# E17-06-PDU_E17-PDU-POWER.net
KiCad netlist of a schematic drawn in Altium Designer
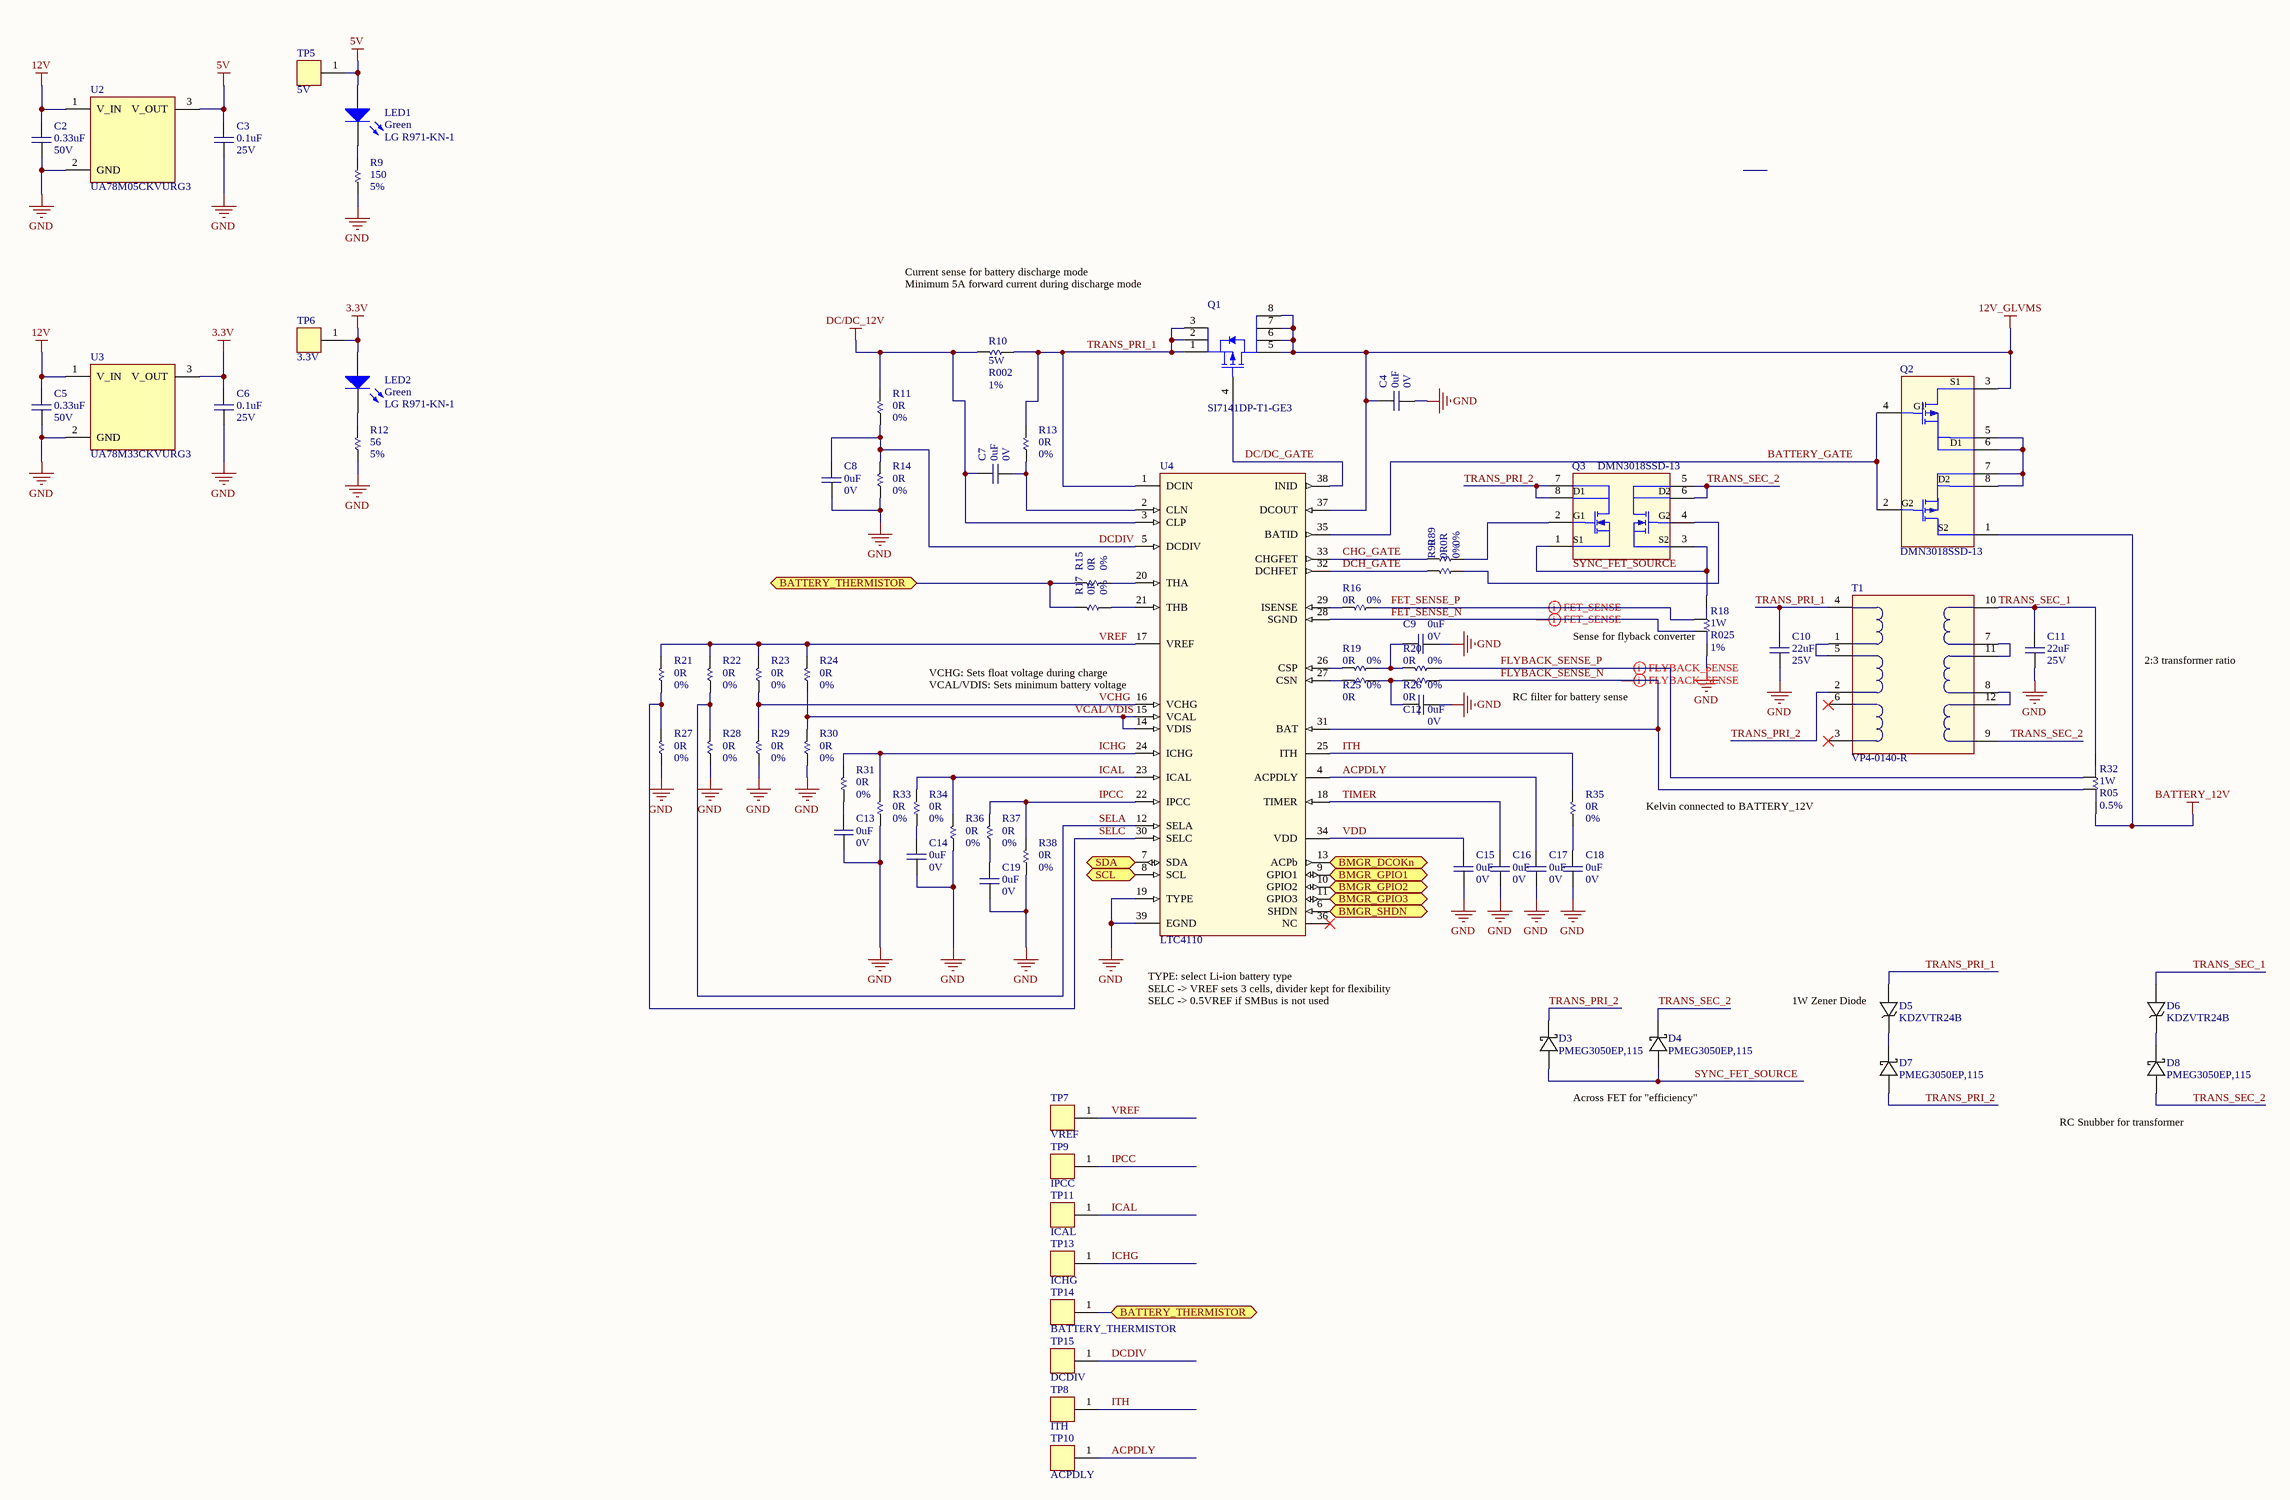
[diagram p0: E17-06-PDU_E17-PDU-POWER.SchDoc]

(export (version "E")
  (design (tool "Eeschema 10.0.6"))
  (components
    (comp (ref "C2")
      (value "0.33uF")
      (footprint "C0805")
      (description "Generic 0805 Capacitor")
      (fields
        (field (name "TOLERANCE") "10%")
        (field (name "VOLTAGE") "50V")
        (field (name "Comment") "C_0805_Generic")
      )
      (libsource (lib "Compiled_PDU") (part "C_0805_Generic"))
    )
    (comp (ref "C3")
      (value "0.1uF")
      (footprint "C0805")
      (description "Generic 0805 Capacitor")
      (fields
        (field (name "TOLERANCE") "10%")
        (field (name "VOLTAGE") "25V")
        (field (name "Comment") "C_0805_Generic")
      )
      (libsource (lib "Compiled_PDU") (part "C_0805_Generic"))
    )
    (comp (ref "C4")
      (value "0uF")
      (footprint "C0603")
      (description "Generic 0603 Capacitor")
      (fields
        (field (name "TOLERANCE") "0%")
        (field (name "VOLTAGE") "0V")
        (field (name "Comment") "C_0603_Generic_1")
      )
      (libsource (lib "Compiled_PDU") (part "C_0603_Generic_1"))
    )
    (comp (ref "C5")
      (value "0.33uF")
      (footprint "C0805")
      (description "Generic 0805 Capacitor")
      (fields
        (field (name "TOLERANCE") "10%")
        (field (name "VOLTAGE") "50V")
        (field (name "Comment") "C_0805_Generic")
      )
      (libsource (lib "Compiled_PDU") (part "C_0805_Generic"))
    )
    (comp (ref "C6")
      (value "0.1uF")
      (footprint "C0805")
      (description "Generic 0805 Capacitor")
      (fields
        (field (name "TOLERANCE") "10%")
        (field (name "VOLTAGE") "25V")
        (field (name "Comment") "C_0805_Generic")
      )
      (libsource (lib "Compiled_PDU") (part "C_0805_Generic"))
    )
    (comp (ref "C7")
      (value "0uF")
      (footprint "C0603")
      (description "Generic 0603 Capacitor")
      (fields
        (field (name "TOLERANCE") "0%")
        (field (name "VOLTAGE") "0V")
        (field (name "Comment") "C_0603_Generic_1")
      )
      (libsource (lib "Compiled_PDU") (part "C_0603_Generic_1"))
    )
    (comp (ref "C8")
      (value "0uF")
      (footprint "C0603")
      (description "Generic 0603 Capacitor")
      (fields
        (field (name "TOLERANCE") "0%")
        (field (name "VOLTAGE") "0V")
        (field (name "Comment") "C_0603_Generic_1")
      )
      (libsource (lib "Compiled_PDU") (part "C_0603_Generic_1"))
    )
    (comp (ref "C9")
      (value "0uF")
      (footprint "C0402")
      (description "Generic 0402 Capacitor")
      (fields
        (field (name "TOLERANCE") "0%")
        (field (name "VOLTAGE") "0V")
        (field (name "Comment") "C_0403_Generic")
      )
      (libsource (lib "Compiled_PDU") (part "C_0403_Generic"))
    )
    (comp (ref "C10")
      (value "22uF")
      (footprint "C0805")
      (description "Generic 0805 Capacitor")
      (fields
        (field (name "TOLERANCE") "20%")
        (field (name "VOLTAGE") "25V")
        (field (name "Comment") "C_0805_Generic")
      )
      (libsource (lib "Compiled_PDU") (part "C_0805_Generic"))
    )
    (comp (ref "C11")
      (value "22uF")
      (footprint "C0805")
      (description "Generic 0805 Capacitor")
      (fields
        (field (name "TOLERANCE") "20%")
        (field (name "VOLTAGE") "25V")
        (field (name "Comment") "C_0805_Generic")
      )
      (libsource (lib "Compiled_PDU") (part "C_0805_Generic"))
    )
    (comp (ref "C12")
      (value "0uF")
      (footprint "C0402")
      (description "Generic 0402 Capacitor")
      (fields
        (field (name "TOLERANCE") "0%")
        (field (name "VOLTAGE") "0V")
        (field (name "Comment") "C_0403_Generic")
      )
      (libsource (lib "Compiled_PDU") (part "C_0403_Generic"))
    )
    (comp (ref "C13")
      (value "0uF")
      (footprint "C0402")
      (description "Generic 0402 Capacitor")
      (fields
        (field (name "TOLERANCE") "0%")
        (field (name "VOLTAGE") "0V")
        (field (name "Comment") "C_0403_Generic")
      )
      (libsource (lib "Compiled_PDU") (part "C_0403_Generic"))
    )
    (comp (ref "C14")
      (value "0uF")
      (footprint "C0402")
      (description "Generic 0402 Capacitor")
      (fields
        (field (name "TOLERANCE") "0%")
        (field (name "VOLTAGE") "0V")
        (field (name "Comment") "C_0403_Generic")
      )
      (libsource (lib "Compiled_PDU") (part "C_0403_Generic"))
    )
    (comp (ref "C15")
      (value "0uF")
      (footprint "C0603")
      (description "Generic 0603 Capacitor")
      (fields
        (field (name "TOLERANCE") "0%")
        (field (name "VOLTAGE") "0V")
        (field (name "Comment") "C_0603_Generic_1")
      )
      (libsource (lib "Compiled_PDU") (part "C_0603_Generic_1"))
    )
    (comp (ref "C16")
      (value "0uF")
      (footprint "C0402")
      (description "Generic 0402 Capacitor")
      (fields
        (field (name "TOLERANCE") "0%")
        (field (name "VOLTAGE") "0V")
        (field (name "Comment") "C_0403_Generic")
      )
      (libsource (lib "Compiled_PDU") (part "C_0403_Generic"))
    )
    (comp (ref "C17")
      (value "0uF")
      (footprint "C0402")
      (description "Generic 0402 Capacitor")
      (fields
        (field (name "TOLERANCE") "0%")
        (field (name "VOLTAGE") "0V")
        (field (name "Comment") "C_0403_Generic")
      )
      (libsource (lib "Compiled_PDU") (part "C_0403_Generic"))
    )
    (comp (ref "C18")
      (value "0uF")
      (footprint "C0402")
      (description "Generic 0402 Capacitor")
      (fields
        (field (name "TOLERANCE") "0%")
        (field (name "VOLTAGE") "0V")
        (field (name "Comment") "C_0403_Generic")
      )
      (libsource (lib "Compiled_PDU") (part "C_0403_Generic"))
    )
    (comp (ref "C19")
      (value "0uF")
      (footprint "C0402")
      (description "Generic 0402 Capacitor")
      (fields
        (field (name "TOLERANCE") "0%")
        (field (name "VOLTAGE") "0V")
        (field (name "Comment") "C_0403_Generic")
      )
      (libsource (lib "Compiled_PDU") (part "C_0403_Generic"))
    )
    (comp (ref "D3")
      (value "D_PMEG3050EP,115")
      (footprint "SOD-128")
      (description "DIODE SCHOTTKY 360mV 30V 5A")
      (fields (field (name "MFG") "Nexperia") (field (name "MFG_PN") "PMEG3050EP,115"))
      (libsource (lib "Compiled_PDU") (part "D_PMEG3050EP,115"))
    )
    (comp (ref "D4")
      (value "D_PMEG3050EP,115")
      (footprint "SOD-128")
      (description "DIODE SCHOTTKY 360mV 30V 5A")
      (fields (field (name "MFG") "Nexperia") (field (name "MFG_PN") "PMEG3050EP,115"))
      (libsource (lib "Compiled_PDU") (part "D_PMEG3050EP,115"))
    )
    (comp (ref "D5")
      (value "D_ZENER")
      (footprint "Compiled_PDU:SOD-123FL")
      (description "DIODE ZENER 24V 1W PMDU")
      (fields (field (name "MFG") "Rohm Semiconductor") (field (name "MFG_PN") "KDZVTR24B"))
      (libsource (lib "Compiled_PDU") (part "D_ZENER"))
    )
    (comp (ref "D6")
      (value "D_ZENER")
      (footprint "Compiled_PDU:SOD-123FL")
      (description "DIODE ZENER 24V 1W PMDU")
      (fields (field (name "MFG") "Rohm Semiconductor") (field (name "MFG_PN") "KDZVTR24B"))
      (libsource (lib "Compiled_PDU") (part "D_ZENER"))
    )
    (comp (ref "D7")
      (value "D_PMEG3050EP,115")
      (footprint "SOD-128")
      (description "DIODE SCHOTTKY 360mV 30V 5A")
      (fields (field (name "MFG") "Nexperia") (field (name "MFG_PN") "PMEG3050EP,115"))
      (libsource (lib "Compiled_PDU") (part "D_PMEG3050EP,115"))
    )
    (comp (ref "D8")
      (value "D_PMEG3050EP,115")
      (footprint "SOD-128")
      (description "DIODE SCHOTTKY 360mV 30V 5A")
      (fields (field (name "MFG") "Nexperia") (field (name "MFG_PN") "PMEG3050EP,115"))
      (libsource (lib "Compiled_PDU") (part "D_PMEG3050EP,115"))
    )
    (comp (ref "LED1")
      (value "Green")
      (footprint "LGR971")
      (description "Green LED")
      (fields (field (name "MFG") "OSRAM Opto Semiconductors Inc.") (field (name "MFG_PN") "LG R971-KN-1"))
      (libsource (lib "Compiled_PDU") (part "LED_LGR971"))
    )
    (comp (ref "LED2")
      (value "Green")
      (footprint "LGR971")
      (description "Green LED")
      (fields (field (name "MFG") "OSRAM Opto Semiconductors Inc.") (field (name "MFG_PN") "LG R971-KN-1"))
      (libsource (lib "Compiled_PDU") (part "LED_LGR971"))
    )
    (comp (ref "Q1")
      (value "Q_SI7141DP-T1-GE3")
      (footprint "PowerPak SO-8")
      (description "P-CH 20V 60A PowerPak SO-8")
      (fields (field (name "MFG") "Vishay") (field (name "MFG_PN") "SI7141DP-T1-GE3"))
      (libsource (lib "Compiled_PDU") (part "Q_SI7141DP-T1-GE3"))
    )
    (comp (ref "Q2")
      (value "Q_DMN3018SSD-13_1")
      (footprint "8-SOIC")
      (description "2x P-ch FET 40V 6.7A")
      (fields (field (name "MFG") "ON Semiconductor") (field (name "MFG_PN") "DMN3018SSD-13"))
      (libsource (lib "Compiled_PDU") (part "Q_DMN3018SSD-13_1"))
    )
    (comp (ref "Q3")
      (value "Q_DMN3018SSD-13")
      (footprint "8-SOIC")
      (description "2x N-ch FET 40V 6.7A")
      (fields (field (name "MFG") "ON Semiconductor") (field (name "MFG_PN") "DMN3018SSD-13"))
      (libsource (lib "Compiled_PDU") (part "Q_DMN3018SSD-13"))
    )
    (comp (ref "R9")
      (value "150")
      (footprint "R0805")
      (description "Generic 0805 Resistor")
      (fields
        (field (name "POWER") "1/8W")
        (field (name "TOLERANCE") "5%")
        (field (name "Comment") "R_0805_Generic")
      )
      (libsource (lib "Compiled_PDU") (part "R_0805_Generic"))
    )
    (comp (ref "R10")
      (value "R002")
      (footprint "R2526")
      (description "RES CURRENT SENSE R002 1% 5W")
      (fields
        (field (name "MFG") "Panasonic")
        (field (name "POWER") "5W")
        (field (name "TOLERANCE") "1%")
        (field (name "Comment") "R_ERJ-MS6SF2M0U")
      )
      (libsource (lib "Compiled_PDU") (part "R_ERJ-MS6SF2M0U"))
    )
    (comp (ref "R11")
      (value "0R")
      (footprint "R0603")
      (description "Generic 0603 Resistor")
      (fields
        (field (name "POWER") "0W")
        (field (name "TOLERANCE") "0%")
        (field (name "Comment") "R_0603_Generic")
      )
      (libsource (lib "Compiled_PDU") (part "R_0603_Generic"))
    )
    (comp (ref "R12")
      (value "56")
      (footprint "R0805")
      (description "Generic 0805 Resistor")
      (fields
        (field (name "POWER") "1/8W")
        (field (name "TOLERANCE") "5%")
        (field (name "Comment") "R_0805_Generic")
      )
      (libsource (lib "Compiled_PDU") (part "R_0805_Generic"))
    )
    (comp (ref "R13")
      (value "0R")
      (footprint "R0603")
      (description "Generic 0603 Resistor")
      (fields
        (field (name "POWER") "0W")
        (field (name "TOLERANCE") "0%")
        (field (name "Comment") "R_0603_Generic")
      )
      (libsource (lib "Compiled_PDU") (part "R_0603_Generic"))
    )
    (comp (ref "R14")
      (value "0R")
      (footprint "R0603")
      (description "Generic 0603 Resistor")
      (fields
        (field (name "POWER") "0W")
        (field (name "TOLERANCE") "0%")
        (field (name "Comment") "R_0603_Generic")
      )
      (libsource (lib "Compiled_PDU") (part "R_0603_Generic"))
    )
    (comp (ref "R15")
      (value "0R")
      (footprint "R0603")
      (description "Generic 0603 Resistor")
      (fields
        (field (name "POWER") "0W")
        (field (name "TOLERANCE") "0%")
        (field (name "Comment") "R_0603_Generic")
      )
      (libsource (lib "Compiled_PDU") (part "R_0603_Generic"))
    )
    (comp (ref "R16")
      (value "0R")
      (footprint "R0402")
      (description "Generic 0402 Resistor")
      (fields
        (field (name "POWER") "0W")
        (field (name "TOLERANCE") "0%")
        (field (name "Comment") "R_0402_Generic")
      )
      (libsource (lib "Compiled_PDU") (part "R_0402_Generic"))
    )
    (comp (ref "R17")
      (value "0R")
      (footprint "R0603")
      (description "Generic 0603 Resistor")
      (fields
        (field (name "POWER") "0W")
        (field (name "TOLERANCE") "0%")
        (field (name "Comment") "R_0603_Generic")
      )
      (libsource (lib "Compiled_PDU") (part "R_0603_Generic"))
    )
    (comp (ref "R18")
      (value "R025")
      (footprint "R2512")
      (description "RES CURRENT SENSE R025 1% 1W")
      (fields
        (field (name "MFG") "Ohmite")
        (field (name "POWER") "1W")
        (field (name "TOLERANCE") "1%")
        (field (name "Comment") "R_LVK24R025FER")
      )
      (libsource (lib "Compiled_PDU") (part "R_LVK24R025FER"))
    )
    (comp (ref "R19")
      (value "0R")
      (footprint "R0402")
      (description "Generic 0402 Resistor")
      (fields
        (field (name "POWER") "0W")
        (field (name "TOLERANCE") "0%")
        (field (name "Comment") "R_0402_Generic")
      )
      (libsource (lib "Compiled_PDU") (part "R_0402_Generic"))
    )
    (comp (ref "R20")
      (value "0R")
      (footprint "R0402")
      (description "Generic 0402 Resistor")
      (fields
        (field (name "POWER") "0W")
        (field (name "TOLERANCE") "0%")
        (field (name "Comment") "R_0402_Generic")
      )
      (libsource (lib "Compiled_PDU") (part "R_0402_Generic"))
    )
    (comp (ref "R21")
      (value "0R")
      (footprint "R0402")
      (description "Generic 0402 Resistor")
      (fields
        (field (name "POWER") "0W")
        (field (name "TOLERANCE") "0%")
        (field (name "Comment") "R_0402_Generic")
      )
      (libsource (lib "Compiled_PDU") (part "R_0402_Generic"))
    )
    (comp (ref "R22")
      (value "0R")
      (footprint "R0402")
      (description "Generic 0402 Resistor")
      (fields
        (field (name "POWER") "0W")
        (field (name "TOLERANCE") "0%")
        (field (name "Comment") "R_0402_Generic")
      )
      (libsource (lib "Compiled_PDU") (part "R_0402_Generic"))
    )
    (comp (ref "R23")
      (value "0R")
      (footprint "R0402")
      (description "Generic 0402 Resistor")
      (fields
        (field (name "POWER") "0W")
        (field (name "TOLERANCE") "0%")
        (field (name "Comment") "R_0402_Generic")
      )
      (libsource (lib "Compiled_PDU") (part "R_0402_Generic"))
    )
    (comp (ref "R24")
      (value "0R")
      (footprint "R0402")
      (description "Generic 0402 Resistor")
      (fields
        (field (name "POWER") "0W")
        (field (name "TOLERANCE") "0%")
        (field (name "Comment") "R_0402_Generic")
      )
      (libsource (lib "Compiled_PDU") (part "R_0402_Generic"))
    )
    (comp (ref "R25")
      (value "0R")
      (footprint "R0402")
      (description "Generic 0402 Resistor")
      (fields
        (field (name "POWER") "0W")
        (field (name "TOLERANCE") "0%")
        (field (name "Comment") "R_0402_Generic")
      )
      (libsource (lib "Compiled_PDU") (part "R_0402_Generic"))
    )
    (comp (ref "R26")
      (value "0R")
      (footprint "R0402")
      (description "Generic 0402 Resistor")
      (fields
        (field (name "POWER") "0W")
        (field (name "TOLERANCE") "0%")
        (field (name "Comment") "R_0402_Generic")
      )
      (libsource (lib "Compiled_PDU") (part "R_0402_Generic"))
    )
    (comp (ref "R27")
      (value "0R")
      (footprint "R0402")
      (description "Generic 0402 Resistor")
      (fields
        (field (name "POWER") "0W")
        (field (name "TOLERANCE") "0%")
        (field (name "Comment") "R_0402_Generic")
      )
      (libsource (lib "Compiled_PDU") (part "R_0402_Generic"))
    )
    (comp (ref "R28")
      (value "0R")
      (footprint "R0402")
      (description "Generic 0402 Resistor")
      (fields
        (field (name "POWER") "0W")
        (field (name "TOLERANCE") "0%")
        (field (name "Comment") "R_0402_Generic")
      )
      (libsource (lib "Compiled_PDU") (part "R_0402_Generic"))
    )
    (comp (ref "R29")
      (value "0R")
      (footprint "R0402")
      (description "Generic 0402 Resistor")
      (fields
        (field (name "POWER") "0W")
        (field (name "TOLERANCE") "0%")
        (field (name "Comment") "R_0402_Generic")
      )
      (libsource (lib "Compiled_PDU") (part "R_0402_Generic"))
    )
    (comp (ref "R30")
      (value "0R")
      (footprint "R0402")
      (description "Generic 0402 Resistor")
      (fields
        (field (name "POWER") "0W")
        (field (name "TOLERANCE") "0%")
        (field (name "Comment") "R_0402_Generic")
      )
      (libsource (lib "Compiled_PDU") (part "R_0402_Generic"))
    )
    (comp (ref "R31")
      (value "0R")
      (footprint "R0402")
      (description "Generic 0402 Resistor")
      (fields
        (field (name "POWER") "0W")
        (field (name "TOLERANCE") "0%")
        (field (name "Comment") "R_0402_Generic")
      )
      (libsource (lib "Compiled_PDU") (part "R_0402_Generic"))
    )
    (comp (ref "R32")
      (value "R05")
      (footprint "R2512")
      (description "RES CURRENT SENSE R05 0.5% 1W")
      (fields
        (field (name "MFG") "Ohmite")
        (field (name "POWER") "1W")
        (field (name "TOLERANCE") "0.5%")
        (field (name "Comment") "R_LVK24R050DER")
      )
      (libsource (lib "Compiled_PDU") (part "R_LVK24R050DER"))
    )
    (comp (ref "R33")
      (value "0R")
      (footprint "R0402")
      (description "Generic 0402 Resistor")
      (fields
        (field (name "POWER") "0W")
        (field (name "TOLERANCE") "0%")
        (field (name "Comment") "R_0402_Generic")
      )
      (libsource (lib "Compiled_PDU") (part "R_0402_Generic"))
    )
    (comp (ref "R34")
      (value "0R")
      (footprint "R0402")
      (description "Generic 0402 Resistor")
      (fields
        (field (name "POWER") "0W")
        (field (name "TOLERANCE") "0%")
        (field (name "Comment") "R_0402_Generic")
      )
      (libsource (lib "Compiled_PDU") (part "R_0402_Generic"))
    )
    (comp (ref "R35")
      (value "0R")
      (footprint "R0402")
      (description "Generic 0402 Resistor")
      (fields
        (field (name "POWER") "0W")
        (field (name "TOLERANCE") "0%")
        (field (name "Comment") "R_0402_Generic")
      )
      (libsource (lib "Compiled_PDU") (part "R_0402_Generic"))
    )
    (comp (ref "R36")
      (value "0R")
      (footprint "R0402")
      (description "Generic 0402 Resistor")
      (fields
        (field (name "POWER") "0W")
        (field (name "TOLERANCE") "0%")
        (field (name "Comment") "R_0402_Generic")
      )
      (libsource (lib "Compiled_PDU") (part "R_0402_Generic"))
    )
    (comp (ref "R37")
      (value "0R")
      (footprint "R0402")
      (description "Generic 0402 Resistor")
      (fields
        (field (name "POWER") "0W")
        (field (name "TOLERANCE") "0%")
        (field (name "Comment") "R_0402_Generic")
      )
      (libsource (lib "Compiled_PDU") (part "R_0402_Generic"))
    )
    (comp (ref "R38")
      (value "0R")
      (footprint "R0402")
      (description "Generic 0402 Resistor")
      (fields
        (field (name "POWER") "0W")
        (field (name "TOLERANCE") "0%")
        (field (name "Comment") "R_0402_Generic")
      )
      (libsource (lib "Compiled_PDU") (part "R_0402_Generic"))
    )
    (comp (ref "R89")
      (value "0R")
      (footprint "R0603")
      (description "Generic 0603 Resistor")
      (fields
        (field (name "POWER") "0W")
        (field (name "TOLERANCE") "0%")
        (field (name "Comment") "R_0603_Generic")
      )
      (libsource (lib "Compiled_PDU") (part "R_0603_Generic"))
    )
    (comp (ref "R90")
      (value "0R")
      (footprint "R0603")
      (description "Generic 0603 Resistor")
      (fields
        (field (name "POWER") "0W")
        (field (name "TOLERANCE") "0%")
        (field (name "Comment") "R_0603_Generic")
      )
      (libsource (lib "Compiled_PDU") (part "R_0603_Generic"))
    )
    (comp (ref "T1")
      (value "T_VP4-0140-R")
      (footprint "T_VP4-0140-R")
      (description "Transformer 6 coil 11.3uH")
      (fields (field (name "MFG") "Eaton") (field (name "MFG_PN") "VP4-0140-R"))
      (libsource (lib "Compiled_PDU") (part "T_VP4-0140-R"))
    )
    (comp (ref "TP5")
      (value "5V")
      (footprint "TEST POINT")
      (description "Test Point")
      (libsource (lib "Compiled_PDU") (part "Test Point"))
    )
    (comp (ref "TP6")
      (value "3.3V")
      (footprint "TEST POINT")
      (description "Test Point")
      (libsource (lib "Compiled_PDU") (part "Test Point"))
    )
    (comp (ref "TP7")
      (value "VREF")
      (footprint "TEST POINT")
      (description "Test Point")
      (libsource (lib "Compiled_PDU") (part "Test Point"))
    )
    (comp (ref "TP8")
      (value "ITH")
      (footprint "TEST POINT")
      (description "Test Point")
      (libsource (lib "Compiled_PDU") (part "Test Point"))
    )
    (comp (ref "TP9")
      (value "IPCC")
      (footprint "TEST POINT")
      (description "Test Point")
      (libsource (lib "Compiled_PDU") (part "Test Point"))
    )
    (comp (ref "TP10")
      (value "ACPDLY")
      (footprint "TEST POINT")
      (description "Test Point")
      (libsource (lib "Compiled_PDU") (part "Test Point"))
    )
    (comp (ref "TP11")
      (value "ICAL")
      (footprint "TEST POINT")
      (description "Test Point")
      (libsource (lib "Compiled_PDU") (part "Test Point"))
    )
    (comp (ref "TP13")
      (value "ICHG")
      (footprint "TEST POINT")
      (description "Test Point")
      (libsource (lib "Compiled_PDU") (part "Test Point"))
    )
    (comp (ref "TP14")
      (value "BATTERY_THERMISTOR")
      (footprint "TEST POINT")
      (description "Test Point")
      (libsource (lib "Compiled_PDU") (part "Test Point"))
    )
    (comp (ref "TP15")
      (value "DCDIV")
      (footprint "TEST POINT")
      (description "Test Point")
      (libsource (lib "Compiled_PDU") (part "Test Point"))
    )
    (comp (ref "U2")
      (value "U_UA78M05CKVURG3")
      (footprint "TO-252-3")
      (description "5V 500mA Linear Regulator")
      (fields (field (name "MFG") "TI") (field (name "MFG_PN") "UA78M05CKVURG3"))
      (libsource (lib "Compiled_PDU") (part "U_UA78M05CKVURG3"))
    )
    (comp (ref "U3")
      (value "U_UA78M33CKVURG3")
      (footprint "TO-252-3")
      (description "3.3V 500mA Linear Regulator")
      (fields (field (name "MFG") "TI") (field (name "MFG_PN") "UA78M33CKVURG3"))
      (libsource (lib "Compiled_PDU") (part "U_UA78M33CKVURG3"))
    )
    (comp (ref "U4")
      (value "U_LTC4110")
      (footprint "U_LTC4110")
      (description "IC Battery Backup Manager")
      (fields (field (name "MFG") "Linear Technology") (field (name "MFG_PN") "LTC4110"))
      (libsource (lib "Compiled_PDU") (part "U_LTC4110"))
    )
  )
  (nets
    (net (code "1") (name "/ACPDLY") (class "Default")
      (node (ref "C17") (pin "1") (pinfunction "EGND_1") (pintype "passive"))
      (node (ref "TP10") (pin "1") (pintype "passive"))
      (node (ref "U4") (pin "4") (pinfunction "ACPDLY_4") (pintype "passive"))
    )
    (net (code "2") (name "/BATTERY_GATE") (class "Default")
      (node (ref "Q2") (pin "2") (pintype "passive"))
      (node (ref "Q2") (pin "4") (pinfunction "4_4") (pintype "passive"))
      (node (ref "U4") (pin "35") (pinfunction "BATID_35") (pintype "output"))
    )
    (net (code "3") (name "/BATTERY_THERMISTOR") (class "Default")
      (node (ref "R15") (pin "1") (pinfunction "1_1") (pintype "passive"))
      (node (ref "R17") (pin "1") (pinfunction "1_1") (pintype "passive"))
      (node (ref "TP14") (pin "1") (pintype "passive"))
    )
    (net (code "4") (name "/BMGR_DCOKn") (class "Default")
      (node (ref "U4") (pin "13") (pinfunction "ACPb_13") (pintype "output"))
    )
    (net (code "5") (name "/BMGR_GPIO1") (class "Default")
      (node (ref "U4") (pin "9") (pinfunction "GPIO1_9") (pintype "bidirectional"))
    )
    (net (code "6") (name "/BMGR_GPIO2") (class "Default")
      (node (ref "U4") (pin "10") (pinfunction "GPIO2_10") (pintype "bidirectional"))
    )
    (net (code "7") (name "/BMGR_GPIO3") (class "Default")
      (node (ref "U4") (pin "11") (pinfunction "GPIO3_11") (pintype "bidirectional"))
    )
    (net (code "8") (name "/BMGR_SHDN") (class "Default")
      (node (ref "U4") (pin "6") (pinfunction "SHDN_6") (pintype "input"))
    )
    (net (code "9") (name "/CHG_GATE") (class "Default")
      (node (ref "R89") (pin "1") (pinfunction "1_1") (pintype "passive"))
      (node (ref "U4") (pin "33") (pinfunction "CHGFET_33") (pintype "output"))
    )
    (net (code "10") (name "/DCDIV") (class "Default")
      (node (ref "C8") (pin "1") (pinfunction "EGND_1") (pintype "passive"))
      (node (ref "R11") (pin "2") (pinfunction "2_2") (pintype "passive"))
      (node (ref "R14") (pin "1") (pinfunction "1_1") (pintype "passive"))
      (node (ref "TP15") (pin "1") (pintype "passive"))
      (node (ref "U4") (pin "5") (pinfunction "DCDIV_5") (pintype "input"))
    )
    (net (code "11") (name "/DCH_GATE") (class "Default")
      (node (ref "R90") (pin "1") (pinfunction "1_1") (pintype "passive"))
      (node (ref "U4") (pin "32") (pinfunction "DCHFET_32") (pintype "output"))
    )
    (net (code "12") (name "/DC{slash}DC_GATE") (class "Default")
      (node (ref "Q1") (pin "4") (pinfunction "G_4") (pintype "passive"))
      (node (ref "U4") (pin "38") (pinfunction "INID_38") (pintype "output"))
    )
    (net (code "13") (name "/FET_SENSE_N") (class "Default")
      (node (ref "R18") (pin "3") (pinfunction "3_3") (pintype "passive"))
      (node (ref "U4") (pin "28") (pinfunction "SGND_28") (pintype "input"))
    )
    (net (code "14") (name "/FET_SENSE_P") (class "Default")
      (node (ref "R16") (pin "2") (pinfunction "2_2") (pintype "passive"))
      (node (ref "R18") (pin "4") (pinfunction "4_4") (pintype "passive"))
    )
    (net (code "15") (name "/FLYBACK_SENSE_N") (class "Default")
      (node (ref "R26") (pin "2") (pinfunction "2_2") (pintype "passive"))
      (node (ref "R32") (pin "3") (pinfunction "3_3") (pintype "passive"))
      (node (ref "U4") (pin "31") (pinfunction "BAT_31") (pintype "input"))
    )
    (net (code "16") (name "/FLYBACK_SENSE_P") (class "Default")
      (node (ref "R20") (pin "2") (pinfunction "2_2") (pintype "passive"))
      (node (ref "R32") (pin "4") (pinfunction "4_4") (pintype "passive"))
    )
    (net (code "17") (name "/ICAL") (class "Default")
      (node (ref "R34") (pin "1") (pinfunction "1_1") (pintype "passive"))
      (node (ref "R36") (pin "1") (pinfunction "1_1") (pintype "passive"))
      (node (ref "TP11") (pin "1") (pintype "passive"))
      (node (ref "U4") (pin "23") (pinfunction "ICAL_23") (pintype "input"))
    )
    (net (code "18") (name "/ICHG") (class "Default")
      (node (ref "R31") (pin "1") (pinfunction "1_1") (pintype "passive"))
      (node (ref "R33") (pin "1") (pinfunction "1_1") (pintype "passive"))
      (node (ref "TP13") (pin "1") (pintype "passive"))
      (node (ref "U4") (pin "24") (pinfunction "ICHG_24") (pintype "input"))
    )
    (net (code "19") (name "/IPCC") (class "Default")
      (node (ref "R37") (pin "1") (pinfunction "1_1") (pintype "passive"))
      (node (ref "R38") (pin "1") (pinfunction "1_1") (pintype "passive"))
      (node (ref "TP9") (pin "1") (pintype "passive"))
      (node (ref "U4") (pin "22") (pinfunction "IPCC_22") (pintype "input"))
    )
    (net (code "20") (name "/ITH") (class "Default")
      (node (ref "R35") (pin "1") (pinfunction "1_1") (pintype "passive"))
      (node (ref "TP8") (pin "1") (pintype "passive"))
      (node (ref "U4") (pin "25") (pinfunction "ITH_25") (pintype "passive"))
    )
    (net (code "21") (name "/SCL") (class "Default")
      (node (ref "U4") (pin "8") (pinfunction "SCL_8") (pintype "input"))
    )
    (net (code "22") (name "/SDA") (class "Default")
      (node (ref "U4") (pin "7") (pinfunction "SDA_7") (pintype "bidirectional"))
    )
    (net (code "23") (name "/SELA") (class "Default")
      (node (ref "R22") (pin "2") (pinfunction "2_2") (pintype "passive"))
      (node (ref "R28") (pin "1") (pinfunction "1_1") (pintype "passive"))
      (node (ref "U4") (pin "12") (pinfunction "SELA_12") (pintype "input"))
    )
    (net (code "24") (name "/SELC") (class "Default")
      (node (ref "R21") (pin "2") (pinfunction "2_2") (pintype "passive"))
      (node (ref "R27") (pin "1") (pinfunction "1_1") (pintype "passive"))
      (node (ref "U4") (pin "30") (pinfunction "SELC_30") (pintype "input"))
    )
    (net (code "25") (name "/SYNC_FET_SOURCE") (class "Default")
      (node (ref "D3") (pin "1") (pintype "passive"))
      (node (ref "D4") (pin "1") (pintype "passive"))
      (node (ref "Q3") (pin "1") (pintype "passive"))
      (node (ref "Q3") (pin "3") (pinfunction "3_3") (pintype "passive"))
      (node (ref "R18") (pin "2") (pinfunction "2_2") (pintype "passive"))
    )
    (net (code "26") (name "/TIMER") (class "Default")
      (node (ref "C16") (pin "1") (pinfunction "EGND_1") (pintype "passive"))
      (node (ref "U4") (pin "18") (pinfunction "TIMER_18") (pintype "input"))
    )
    (net (code "27") (name "/TRANS_PRI_1") (class "Default")
      (node (ref "C10") (pin "1") (pinfunction "EGND_1") (pintype "passive"))
      (node (ref "D5") (pin "1") (pintype "passive"))
      (node (ref "Q1") (pin "1") (pintype "passive"))
      (node (ref "Q1") (pin "2") (pinfunction "5_2") (pintype "passive"))
      (node (ref "Q1") (pin "3") (pinfunction "6_3") (pintype "passive"))
      (node (ref "R10") (pin "2") (pinfunction "2_2") (pintype "passive"))
      (node (ref "R13") (pin "1") (pinfunction "1_1") (pintype "passive"))
      (node (ref "T1") (pin "4") (pinfunction "4_4") (pintype "passive"))
      (node (ref "U4") (pin "1") (pinfunction "DCIN_1") (pintype "power_in"))
    )
    (net (code "28") (name "/TRANS_PRI_2") (class "Default")
      (node (ref "D3") (pin "2") (pintype "passive"))
      (node (ref "D7") (pin "1") (pintype "passive"))
      (node (ref "Q3") (pin "7") (pinfunction "7_7") (pintype "passive"))
      (node (ref "Q3") (pin "8") (pinfunction "8_8") (pintype "passive"))
      (node (ref "T1") (pin "2") (pinfunction "2_2") (pintype "passive"))
    )
    (net (code "29") (name "/TRANS_SEC_1") (class "Default")
      (node (ref "C11") (pin "1") (pinfunction "EGND_1") (pintype "passive"))
      (node (ref "D6") (pin "1") (pintype "passive"))
      (node (ref "R32") (pin "2") (pinfunction "2_2") (pintype "passive"))
      (node (ref "T1") (pin "10") (pinfunction "10_10") (pintype "passive"))
    )
    (net (code "30") (name "/TRANS_SEC_2") (class "Default")
      (node (ref "D4") (pin "2") (pintype "passive"))
      (node (ref "D8") (pin "1") (pintype "passive"))
      (node (ref "Q3") (pin "5") (pinfunction "5_5") (pintype "passive"))
      (node (ref "Q3") (pin "6") (pinfunction "6_6") (pintype "passive"))
      (node (ref "T1") (pin "9") (pinfunction "9_9") (pintype "passive"))
    )
    (net (code "31") (name "/VCAL{slash}VDIS") (class "Default")
      (node (ref "R24") (pin "2") (pinfunction "2_2") (pintype "passive"))
      (node (ref "R30") (pin "1") (pinfunction "1_1") (pintype "passive"))
      (node (ref "U4") (pin "14") (pinfunction "VDIS_14") (pintype "input"))
      (node (ref "U4") (pin "15") (pinfunction "VCAL_15") (pintype "input"))
    )
    (net (code "32") (name "/VCHG") (class "Default")
      (node (ref "R23") (pin "2") (pinfunction "2_2") (pintype "passive"))
      (node (ref "R29") (pin "1") (pinfunction "1_1") (pintype "passive"))
      (node (ref "U4") (pin "16") (pinfunction "VCHG_16") (pintype "input"))
    )
    (net (code "33") (name "/VDD") (class "Default")
      (node (ref "C15") (pin "1") (pinfunction "EGND_1") (pintype "passive"))
      (node (ref "U4") (pin "34") (pinfunction "VDD_34") (pintype "power_in"))
    )
    (net (code "34") (name "/VREF") (class "Default")
      (node (ref "R21") (pin "1") (pinfunction "1_1") (pintype "passive"))
      (node (ref "R22") (pin "1") (pinfunction "1_1") (pintype "passive"))
      (node (ref "R23") (pin "1") (pinfunction "1_1") (pintype "passive"))
      (node (ref "R24") (pin "1") (pinfunction "1_1") (pintype "passive"))
      (node (ref "TP7") (pin "1") (pintype "passive"))
      (node (ref "U4") (pin "17") (pinfunction "VREF_17") (pintype "power_in"))
    )
    (net (code "35") (name "3.3V") (class "Default")
      (node (ref "C6") (pin "1") (pinfunction "EGND_1") (pintype "passive"))
      (node (ref "LED2") (pin "1") (pinfunction "A_1") (pintype "passive"))
      (node (ref "TP6") (pin "1") (pintype "passive"))
      (node (ref "U3") (pin "3") (pinfunction "V_OUT_3") (pintype "power_in"))
    )
    (net (code "36") (name "5V") (class "Default")
      (node (ref "C3") (pin "1") (pinfunction "EGND_1") (pintype "passive"))
      (node (ref "LED1") (pin "1") (pinfunction "A_1") (pintype "passive"))
      (node (ref "TP5") (pin "1") (pintype "passive"))
      (node (ref "U2") (pin "3") (pinfunction "V_OUT_3") (pintype "power_in"))
    )
    (net (code "37") (name "12V") (class "Default")
      (node (ref "C2") (pin "1") (pinfunction "EGND_1") (pintype "passive"))
      (node (ref "C5") (pin "1") (pinfunction "EGND_1") (pintype "passive"))
      (node (ref "U2") (pin "1") (pinfunction "V_IN_1") (pintype "power_in"))
      (node (ref "U3") (pin "1") (pinfunction "V_IN_1") (pintype "passive"))
    )
    (net (code "38") (name "12V_GLVMS") (class "Default")
      (node (ref "C4") (pin "1") (pinfunction "EGND_1") (pintype "passive"))
      (node (ref "Q1") (pin "5") (pinfunction "5_5") (pintype "passive"))
      (node (ref "Q1") (pin "6") (pinfunction "6_6") (pintype "passive"))
      (node (ref "Q1") (pin "7") (pinfunction "7_7") (pintype "passive"))
      (node (ref "Q1") (pin "8") (pinfunction "8_8") (pintype "passive"))
      (node (ref "Q2") (pin "3") (pinfunction "3_3") (pintype "passive"))
      (node (ref "U4") (pin "37") (pinfunction "DCOUT_37") (pintype "input"))
    )
    (net (code "39") (name "BATTERY_12V") (class "Default")
      (node (ref "Q2") (pin "1") (pintype "passive"))
      (node (ref "R32") (pin "1") (pinfunction "1_1") (pintype "passive"))
    )
    (net (code "40") (name "DC{slash}DC_12V") (class "Default")
      (node (ref "C7") (pin "1") (pinfunction "EGND_1") (pintype "passive"))
      (node (ref "R10") (pin "1") (pinfunction "1_1") (pintype "passive"))
      (node (ref "R11") (pin "1") (pinfunction "1_1") (pintype "passive"))
      (node (ref "U4") (pin "3") (pinfunction "CLP_3") (pintype "input"))
    )
    (net (code "41") (name "GND") (class "Default")
      (node (ref "C10") (pin "2") (pinfunction "2_2") (pintype "passive"))
      (node (ref "C11") (pin "2") (pinfunction "2_2") (pintype "passive"))
      (node (ref "C12") (pin "1") (pinfunction "EGND_1") (pintype "passive"))
      (node (ref "C13") (pin "2") (pinfunction "2_2") (pintype "passive"))
      (node (ref "C14") (pin "2") (pinfunction "2_2") (pintype "passive"))
      (node (ref "C15") (pin "2") (pinfunction "2_2") (pintype "passive"))
      (node (ref "C16") (pin "2") (pinfunction "2_2") (pintype "passive"))
      (node (ref "C17") (pin "2") (pinfunction "2_2") (pintype "passive"))
      (node (ref "C18") (pin "2") (pinfunction "2_2") (pintype "passive"))
      (node (ref "C19") (pin "2") (pinfunction "2_2") (pintype "passive"))
      (node (ref "C2") (pin "2") (pinfunction "2_2") (pintype "passive"))
      (node (ref "C3") (pin "2") (pinfunction "2_2") (pintype "passive"))
      (node (ref "C4") (pin "2") (pinfunction "2_2") (pintype "passive"))
      (node (ref "C5") (pin "2") (pinfunction "2_2") (pintype "passive"))
      (node (ref "C6") (pin "2") (pinfunction "2_2") (pintype "passive"))
      (node (ref "C8") (pin "2") (pinfunction "2_2") (pintype "passive"))
      (node (ref "C9") (pin "2") (pinfunction "2_2") (pintype "passive"))
      (node (ref "R12") (pin "2") (pinfunction "2_2") (pintype "passive"))
      (node (ref "R14") (pin "2") (pinfunction "2_2") (pintype "passive"))
      (node (ref "R18") (pin "1") (pinfunction "1_1") (pintype "passive"))
      (node (ref "R27") (pin "2") (pinfunction "2_2") (pintype "passive"))
      (node (ref "R28") (pin "2") (pinfunction "2_2") (pintype "passive"))
      (node (ref "R29") (pin "2") (pinfunction "2_2") (pintype "passive"))
      (node (ref "R30") (pin "2") (pinfunction "2_2") (pintype "passive"))
      (node (ref "R33") (pin "2") (pinfunction "2_2") (pintype "passive"))
      (node (ref "R36") (pin "2") (pinfunction "2_2") (pintype "passive"))
      (node (ref "R38") (pin "2") (pinfunction "2_2") (pintype "passive"))
      (node (ref "R9") (pin "2") (pinfunction "2_2") (pintype "passive"))
      (node (ref "U2") (pin "2") (pinfunction "GND_2") (pintype "power_in"))
      (node (ref "U3") (pin "2") (pinfunction "GND_2") (pintype "power_in"))
      (node (ref "U4") (pin "19") (pinfunction "TYPE_19") (pintype "input"))
      (node (ref "U4") (pin "39") (pinfunction "EGND_39") (pintype "power_in"))
    )
    (net (code "42") (name "Net-(C9-EGND)") (class "Default")
      (node (ref "C9") (pin "1") (pinfunction "EGND_1") (pintype "passive"))
      (node (ref "R19") (pin "2") (pinfunction "2_2") (pintype "passive"))
      (node (ref "R20") (pin "1") (pinfunction "1_1") (pintype "passive"))
    )
    (net (code "43") (name "Net-(C12-Pad2)") (class "Default")
      (node (ref "C12") (pin "2") (pinfunction "2_2") (pintype "passive"))
      (node (ref "R25") (pin "2") (pinfunction "2_2") (pintype "passive"))
      (node (ref "R26") (pin "1") (pinfunction "1_1") (pintype "passive"))
    )
    (net (code "44") (name "Net-(C13-EGND)") (class "Default")
      (node (ref "C13") (pin "1") (pinfunction "EGND_1") (pintype "passive"))
      (node (ref "R31") (pin "2") (pinfunction "2_2") (pintype "passive"))
    )
    (net (code "45") (name "Net-(C14-EGND)") (class "Default")
      (node (ref "C14") (pin "1") (pinfunction "EGND_1") (pintype "passive"))
      (node (ref "R34") (pin "2") (pinfunction "2_2") (pintype "passive"))
    )
    (net (code "46") (name "Net-(C18-EGND)") (class "Default")
      (node (ref "C18") (pin "1") (pinfunction "EGND_1") (pintype "passive"))
      (node (ref "R35") (pin "2") (pinfunction "2_2") (pintype "passive"))
    )
    (net (code "47") (name "Net-(C19-EGND)") (class "Default")
      (node (ref "C19") (pin "1") (pinfunction "EGND_1") (pintype "passive"))
      (node (ref "R37") (pin "2") (pinfunction "2_2") (pintype "passive"))
    )
    (net (code "48") (name "Net-(D5-Pad2)") (class "Default")
      (node (ref "D5") (pin "2") (pintype "passive"))
      (node (ref "D7") (pin "2") (pintype "passive"))
    )
    (net (code "49") (name "Net-(D6-Pad2)") (class "Default")
      (node (ref "D6") (pin "2") (pintype "passive"))
      (node (ref "D8") (pin "2") (pintype "passive"))
    )
    (net (code "50") (name "Net-(LED1-K)") (class "Default")
      (node (ref "LED1") (pin "2") (pinfunction "K_2") (pintype "passive"))
      (node (ref "R9") (pin "1") (pinfunction "1_1") (pintype "passive"))
    )
    (net (code "51") (name "Net-(LED2-K)") (class "Default")
      (node (ref "LED2") (pin "2") (pinfunction "K_2") (pintype "passive"))
      (node (ref "R12") (pin "1") (pinfunction "1_1") (pintype "passive"))
    )
    (net (code "52") (name "Net-(Q2-Pad5)") (class "Default")
      (node (ref "Q2") (pin "5") (pinfunction "5_5") (pintype "passive"))
      (node (ref "Q2") (pin "6") (pinfunction "6_6") (pintype "passive"))
      (node (ref "Q2") (pin "7") (pinfunction "7_7") (pintype "passive"))
      (node (ref "Q2") (pin "8") (pinfunction "8_8") (pintype "passive"))
    )
    (net (code "53") (name "Net-(Q3-Pad2)") (class "Default")
      (node (ref "Q3") (pin "2") (pintype "passive"))
      (node (ref "R89") (pin "2") (pinfunction "2_2") (pintype "passive"))
    )
    (net (code "54") (name "Net-(Q3-Pad4)") (class "Default")
      (node (ref "Q3") (pin "4") (pinfunction "4_4") (pintype "passive"))
      (node (ref "R90") (pin "2") (pinfunction "2_2") (pintype "passive"))
    )
    (net (code "55") (name "Net-(T1-Pad1)") (class "Default")
      (node (ref "T1") (pin "1") (pinfunction "1_1") (pintype "passive"))
      (node (ref "T1") (pin "5") (pinfunction "5_5") (pintype "passive"))
    )
    (net (code "56") (name "Net-(T1-Pad11)") (class "Default")
      (node (ref "T1") (pin "11") (pinfunction "11_11") (pintype "passive"))
      (node (ref "T1") (pin "7") (pinfunction "7_7") (pintype "passive"))
    )
    (net (code "57") (name "Net-(T1-Pad12)") (class "Default")
      (node (ref "T1") (pin "12") (pinfunction "12_12") (pintype "passive"))
      (node (ref "T1") (pin "8") (pinfunction "8_8") (pintype "passive"))
    )
    (net (code "58") (name "Net-(U4-CLN)") (class "Default")
      (node (ref "C7") (pin "2") (pinfunction "2_2") (pintype "passive"))
      (node (ref "R13") (pin "2") (pinfunction "2_2") (pintype "passive"))
      (node (ref "U4") (pin "2") (pinfunction "CLN_2") (pintype "input"))
    )
    (net (code "59") (name "Net-(U4-CSN)") (class "Default")
      (node (ref "R25") (pin "1") (pinfunction "1_1") (pintype "passive"))
      (node (ref "U4") (pin "27") (pinfunction "CSN_27") (pintype "input"))
    )
    (net (code "60") (name "Net-(U4-CSP)") (class "Default")
      (node (ref "R19") (pin "1") (pinfunction "1_1") (pintype "passive"))
      (node (ref "U4") (pin "26") (pinfunction "CSP_26") (pintype "input"))
    )
    (net (code "61") (name "Net-(U4-ISENSE)") (class "Default")
      (node (ref "R16") (pin "1") (pinfunction "1_1") (pintype "passive"))
      (node (ref "U4") (pin "29") (pinfunction "ISENSE_29") (pintype "input"))
    )
    (net (code "62") (name "Net-(U4-THA)") (class "Default")
      (node (ref "R15") (pin "2") (pinfunction "2_2") (pintype "passive"))
      (node (ref "U4") (pin "20") (pinfunction "THA_20") (pintype "input"))
    )
    (net (code "63") (name "Net-(U4-THB)") (class "Default")
      (node (ref "R17") (pin "2") (pinfunction "2_2") (pintype "passive"))
      (node (ref "U4") (pin "21") (pinfunction "THB_21") (pintype "input"))
    )
    (net (code "64") (name "unconnected-(T1-Pad3)") (class "Default")
      (node (ref "T1") (pin "3") (pinfunction "3_3") (pintype "passive+no_connect"))
    )
    (net (code "65") (name "unconnected-(T1-Pad6)") (class "Default")
      (node (ref "T1") (pin "6") (pinfunction "6_6") (pintype "passive+no_connect"))
    )
    (net (code "66") (name "unconnected-(U4-NC-Pad36)") (class "Default")
      (node (ref "U4") (pin "36") (pinfunction "NC_36") (pintype "passive+no_connect"))
    )
  )
)
